# Top_Level.net
KiCad netlist of a schematic drawn in Altium Designer
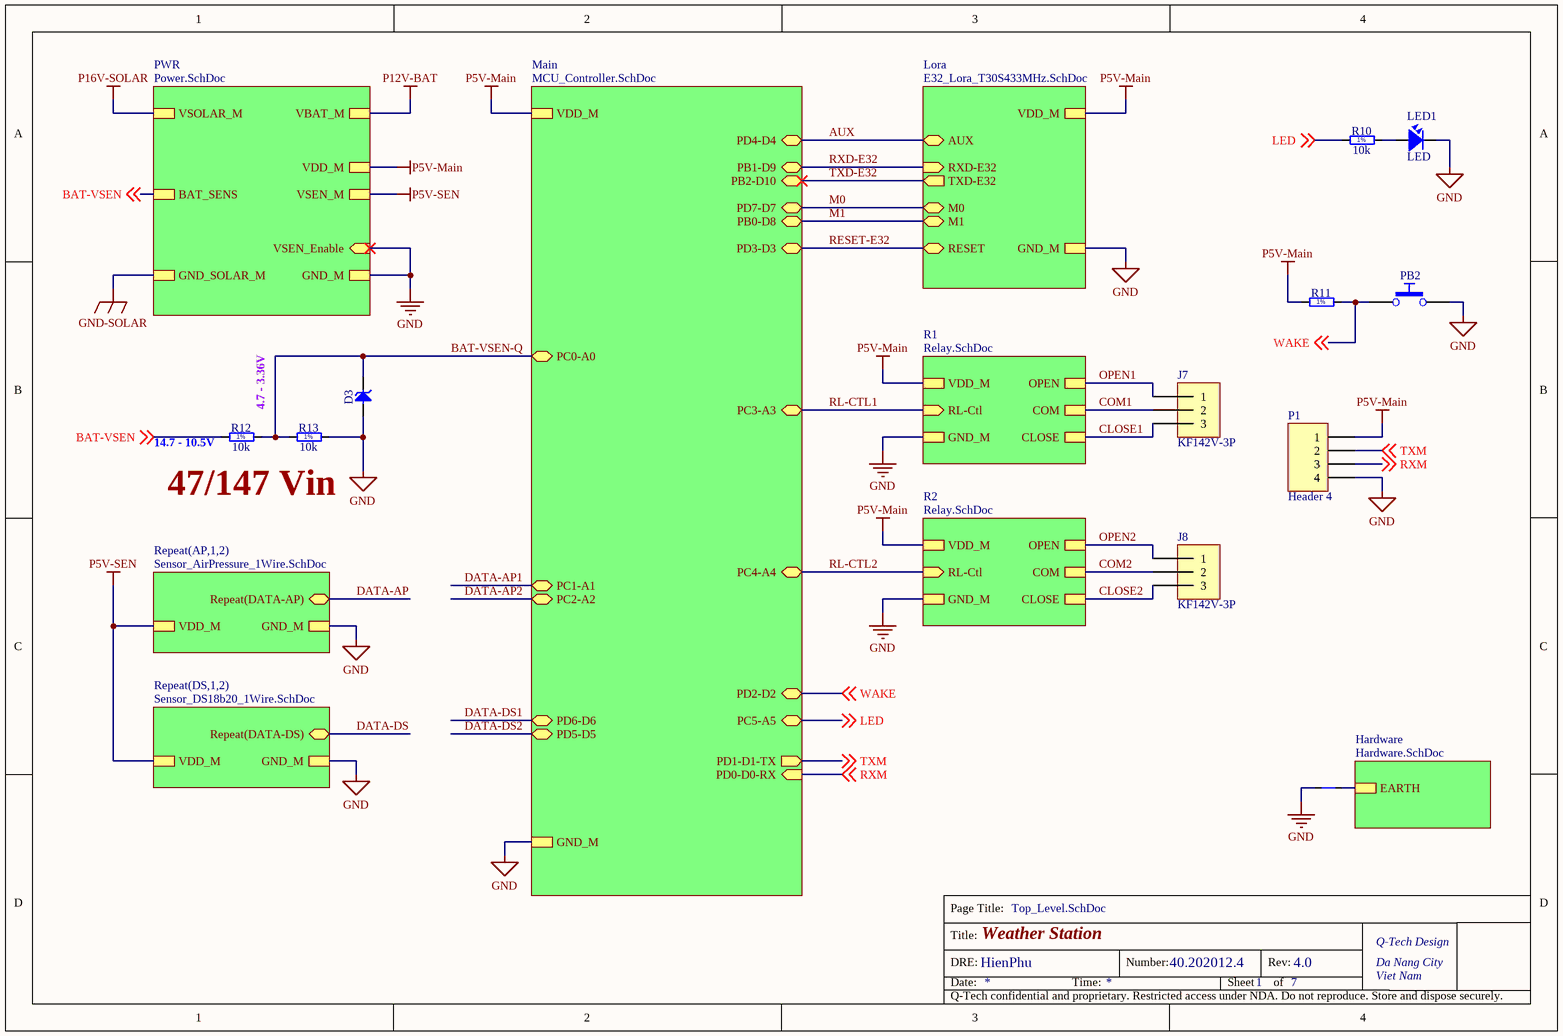
[diagram p0: Top_Level.SchDoc]

(export (version "E")
  (design (tool "Eeschema 10.0.6"))
  (components
    (comp (ref "D3")
      (value "BZV55-B5V1")
      (footprint "DIOMELF3515N")
      (description "Zener Diode")
      (fields
        (field (name "VOLTAGE") "5V1")
        (field (name "POWER") "500mW")
        (field (name "AUTHOR") "CERN DEM JLC")
      )
      (libsource (lib "ICs And Semiconductors") (part "Diode Zener"))
    )
    (comp (ref "J7")
      (value "KF142V-3P")
      (footprint "CON KF142V-3P-5.08")
      (description "CON KF142V-3P-5.08")
      (libsource (lib "alib_pnphien") (part "CON KF142V-3P-5.08"))
    )
    (comp (ref "J8")
      (value "KF142V-3P")
      (footprint "CON KF142V-3P-5.08")
      (description "CON KF142V-3P-5.08")
      (libsource (lib "alib_pnphien") (part "CON KF142V-3P-5.08"))
    )
    (comp (ref "LED1")
      (value "LED")
      (footprint "L-0805")
      (description "LED Single colour Green and Red")
      (libsource (lib "alib_pnphien") (part "LED"))
    )
    (comp (ref "P1")
      (value "Header 4")
      (footprint "HDR1X4")
      (description "Header, 4-Pin")
      (fields (field (name "PUBLISHER") "Altium Limited"))
      (libsource (lib "Miscellaneous Connectors") (part "Header 4"))
    )
    (comp (ref "PB2")
      (value "Push Button")
      (footprint "PB_TYCO_FSMSM")
      (description "Push-Button Switch SPDT")
      (fields
        (field (name "PART NUMBER") "PB_TYCO_FSMSM")
        (field (name "MANUFACTURER") "TYCO ELECTRONICS")
        (field (name "AUTHOR") "CERN DEM JLC")
      )
      (libsource (lib "alib_pnphien") (part "PB SPST 1NO-2NO"))
    )
    (comp (ref "R10")
      (value "10k")
      (footprint "RESC1608X55N")
      (description "Resistor - 1%")
      (fields
        (field (name "PART NUMBER") "R0603_200R_1%_0.1W_100PPM")
        (field (name "POWER") "0.1W")
        (field (name "AUTHOR") "CERN DEM JLC")
      )
      (libsource (lib "Resistors") (part "Resistor - 1%"))
    )
    (comp (ref "R11")
      (value "10k")
      (footprint "RESC1608X55N")
      (description "Resistor - 1%")
      (fields
        (field (name "PART NUMBER") "R0603_10K_1%_0.1W_100PPM")
        (field (name "POWER") "0.1W")
        (field (name "AUTHOR") "CERN DEM JLC")
      )
      (libsource (lib "Resistors") (part "Resistor - 1%"))
    )
    (comp (ref "R12")
      (value "10k")
      (footprint "RESC1608X55N")
      (description "Resistor - 1%")
      (fields
        (field (name "PART NUMBER") "R0603_2M_1%_0.1W_100PPM")
        (field (name "POWER") "0.1W")
        (field (name "AUTHOR") "CERN DEM JLC")
      )
      (libsource (lib "Resistors") (part "Resistor - 1%"))
    )
    (comp (ref "R13")
      (value "10k")
      (footprint "RESC1608X55N")
      (description "Resistor - 1%")
      (fields
        (field (name "PART NUMBER") "R0603_1M_1%_0.1W_100PPM")
        (field (name "POWER") "0.1W")
        (field (name "AUTHOR") "CERN DEM JLC")
      )
      (libsource (lib "Resistors") (part "Resistor - 1%"))
    )
    (comp (ref "TIE1") (value "TIE") (footprint "tie") (libsource (lib "Schlib1") (part "TIE")))
  )
  (nets
    (net (code "3") (name "/BAT-VSEN-Q") (class "Default")
      (node (ref "D3") (pin "1") (pinfunction "C_1") (pintype "passive"))
      (node (ref "R12") (pin "2") (pinfunction "2_2") (pintype "passive"))
      (node (ref "R13") (pin "1") (pinfunction "1_1") (pintype "passive"))
    )
    (net (code "4") (name "/CLOSE1") (class "Default")
      (node (ref "J7") (pin "3") (pinfunction "3_3") (pintype "passive"))
    )
    (net (code "5") (name "/CLOSE2") (class "Default")
      (node (ref "J8") (pin "3") (pinfunction "3_3") (pintype "passive"))
    )
    (net (code "6") (name "/COM1") (class "Default")
      (node (ref "J7") (pin "2") (pinfunction "2_2") (pintype "passive"))
    )
    (net (code "7") (name "/COM2") (class "Default")
      (node (ref "J8") (pin "2") (pinfunction "2_2") (pintype "passive"))
    )
    (net (code "13") (name "/EARTH") (class "Default")
      (node (ref "TIE1") (pin "2") (pinfunction "2_2") (pintype "passive"))
    )
    (net (code "16") (name "/OPEN1") (class "Default")
      (node (ref "J7") (pin "1") (pinfunction "1_1") (pintype "passive"))
    )
    (net (code "17") (name "/OPEN2") (class "Default")
      (node (ref "J8") (pin "1") (pinfunction "1_1") (pintype "passive"))
    )
    (net (code "23") (name "BAT-VSEN") (class "Default")
      (node (ref "R12") (pin "1") (pinfunction "1_1") (pintype "passive"))
    )
    (net (code "24") (name "GND") (class "Default")
      (node (ref "D3") (pin "2") (pinfunction "A_2") (pintype "passive"))
      (node (ref "LED1") (pin "2") (pinfunction "2_2") (pintype "passive"))
      (node (ref "P1") (pin "4") (pinfunction "4_4") (pintype "passive"))
      (node (ref "PB2") (pin "2") (pinfunction "2_2") (pintype "passive"))
      (node (ref "R13") (pin "2") (pinfunction "2_2") (pintype "passive"))
      (node (ref "TIE1") (pin "1") (pinfunction "1_1") (pintype "passive"))
    )
    (net (code "26") (name "LED") (class "Default")
      (node (ref "R10") (pin "1") (pinfunction "1_1") (pintype "passive"))
    )
    (net (code "27") (name "Net-(LED1-Pad1)") (class "Default")
      (node (ref "LED1") (pin "1") (pinfunction "1_1") (pintype "passive"))
      (node (ref "R10") (pin "2") (pinfunction "2_2") (pintype "passive"))
    )
    (net (code "28") (name "P5V-Main") (class "Default")
      (node (ref "P1") (pin "1") (pinfunction "1_1") (pintype "passive"))
      (node (ref "R11") (pin "1") (pinfunction "1_1") (pintype "passive"))
    )
    (net (code "32") (name "RXM") (class "Default")
      (node (ref "P1") (pin "3") (pinfunction "3_3") (pintype "passive"))
    )
    (net (code "33") (name "TXM") (class "Default")
      (node (ref "P1") (pin "2") (pinfunction "2_2") (pintype "passive"))
    )
    (net (code "34") (name "WAKE") (class "Default")
      (node (ref "PB2") (pin "1") (pinfunction "1_1") (pintype "passive"))
      (node (ref "R11") (pin "2") (pinfunction "2_2") (pintype "passive"))
    )
  )
)
